# relay_driver.net
KiCad netlist of a schematic drawn in EAGLE
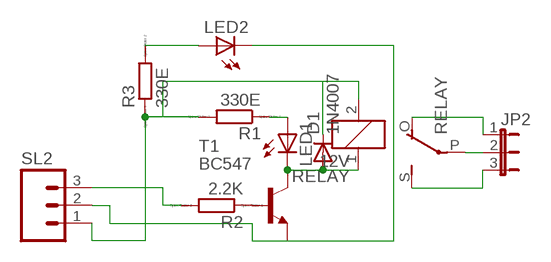
[diagram p0: schematic, sheet 1]

(export (version "E")
  (design (tool "Eeschema 10.0.6"))
  (components
    (comp (ref "D1")
      (value "1N4007")
      (footprint "eagle-import:DO41-10")
      (libsource (lib "eagle-import") (part "1N4004"))
    )
    (comp (ref "JP2")
      (value "JP2E")
      (footprint "eagle-import:JP2")
      (libsource (lib "eagle-import") (part "JP2E"))
    )
    (comp (ref "LED1")
      (value "LED3MM")
      (footprint "eagle-import:LED3MM")
      (libsource (lib "eagle-import") (part "LED3MM"))
    )
    (comp (ref "LED2")
      (value "LED3MM")
      (footprint "eagle-import:LED3MM")
      (libsource (lib "eagle-import") (part "LED3MM"))
    )
    (comp (ref "R1")
      (value "330E")
      (footprint "eagle-import:0204_7")
      (libsource (lib "eagle-import") (part "R0204/7"))
    )
    (comp (ref "R2")
      (value "2.2K")
      (footprint "eagle-import:0204_7")
      (libsource (lib "eagle-import") (part "R0204/7"))
    )
    (comp (ref "R3")
      (value "330E")
      (footprint "eagle-import:0204_7")
      (fields (field (name "SPICEMODEL") "NONE") (field (name "SPICEPREFIX") "R"))
      (libsource (lib "eagle-import") (part "R0204/7"))
    )
    (comp (ref "RELAY")
      (value "12V")
      (footprint "eagle-import:G5LE")
      (libsource (lib "eagle-import") (part "G5L"))
    )
    (comp (ref "SL2")
      (value "M03")
      (footprint "eagle-import:03P")
      (libsource (lib "eagle-import") (part "M03"))
    )
    (comp (ref "T1")
      (value "BC547")
      (footprint "eagle-import:TO92")
      (libsource (lib "eagle-import") (part "BC547"))
    )
  )
  (nets
    (net (code "1") (name "Net-(D1-PadC)") (class "Default")
      (node (ref "D1") (pin "C") (pinfunction "C_C") (pintype "passive"))
      (node (ref "R1") (pin "2") (pinfunction "2_2") (pintype "passive"))
      (node (ref "R3") (pin "1") (pinfunction "1_1") (pintype "passive"))
      (node (ref "RELAY") (pin "2") (pinfunction "2_2") (pintype "passive"))
      (node (ref "SL2") (pin "1") (pinfunction "1_1") (pintype "passive"))
    )
    (net (code "2") (name "Net-(JP2-Pad1)") (class "Default")
      (node (ref "JP2") (pin "1") (pinfunction "1_1") (pintype "passive"))
      (node (ref "RELAY") (pin "O") (pinfunction "O_O") (pintype "passive"))
    )
    (net (code "3") (name "Net-(JP2-Pad2)") (class "Default")
      (node (ref "JP2") (pin "2") (pinfunction "2_2") (pintype "passive"))
      (node (ref "RELAY") (pin "P") (pinfunction "P_P") (pintype "passive"))
    )
    (net (code "4") (name "Net-(JP2-Pad3)") (class "Default")
      (node (ref "JP2") (pin "3") (pinfunction "3_3") (pintype "passive"))
      (node (ref "RELAY") (pin "S") (pinfunction "S_S") (pintype "passive"))
    )
    (net (code "5") (name "Net-(LED1-C)") (class "Default")
      (node (ref "D1") (pin "A") (pinfunction "A_A") (pintype "passive"))
      (node (ref "LED1") (pin "K") (pinfunction "C_K") (pintype "passive"))
      (node (ref "RELAY") (pin "1") (pinfunction "1_1") (pintype "passive"))
      (node (ref "T1") (pin "3") (pinfunction "C_3") (pintype "passive"))
    )
    (net (code "6") (name "Net-(LED1-PadA)") (class "Default")
      (node (ref "LED1") (pin "A") (pinfunction "A_A") (pintype "passive"))
      (node (ref "R1") (pin "1") (pinfunction "1_1") (pintype "passive"))
    )
    (net (code "7") (name "Net-(LED2-C)") (class "Default")
      (node (ref "LED2") (pin "K") (pinfunction "C_K") (pintype "passive"))
      (node (ref "SL2") (pin "2") (pinfunction "2_2") (pintype "passive"))
      (node (ref "T1") (pin "1") (pinfunction "E_1") (pintype "passive"))
    )
    (net (code "8") (name "Net-(LED2-PadA)") (class "Default")
      (node (ref "LED2") (pin "A") (pinfunction "A_A") (pintype "passive"))
      (node (ref "R3") (pin "2") (pinfunction "2_2") (pintype "passive"))
    )
    (net (code "9") (name "Net-(R2-Pad2)") (class "Default")
      (node (ref "R2") (pin "2") (pinfunction "2_2") (pintype "passive"))
      (node (ref "SL2") (pin "3") (pinfunction "3_3") (pintype "passive"))
    )
    (net (code "10") (name "Net-(T1-B)") (class "Default")
      (node (ref "R2") (pin "1") (pinfunction "1_1") (pintype "passive"))
      (node (ref "T1") (pin "2") (pinfunction "B_2") (pintype "passive"))
    )
  )
)
